# LN_LASER_PS.net
KiCad netlist of a schematic drawn in Altium Designer
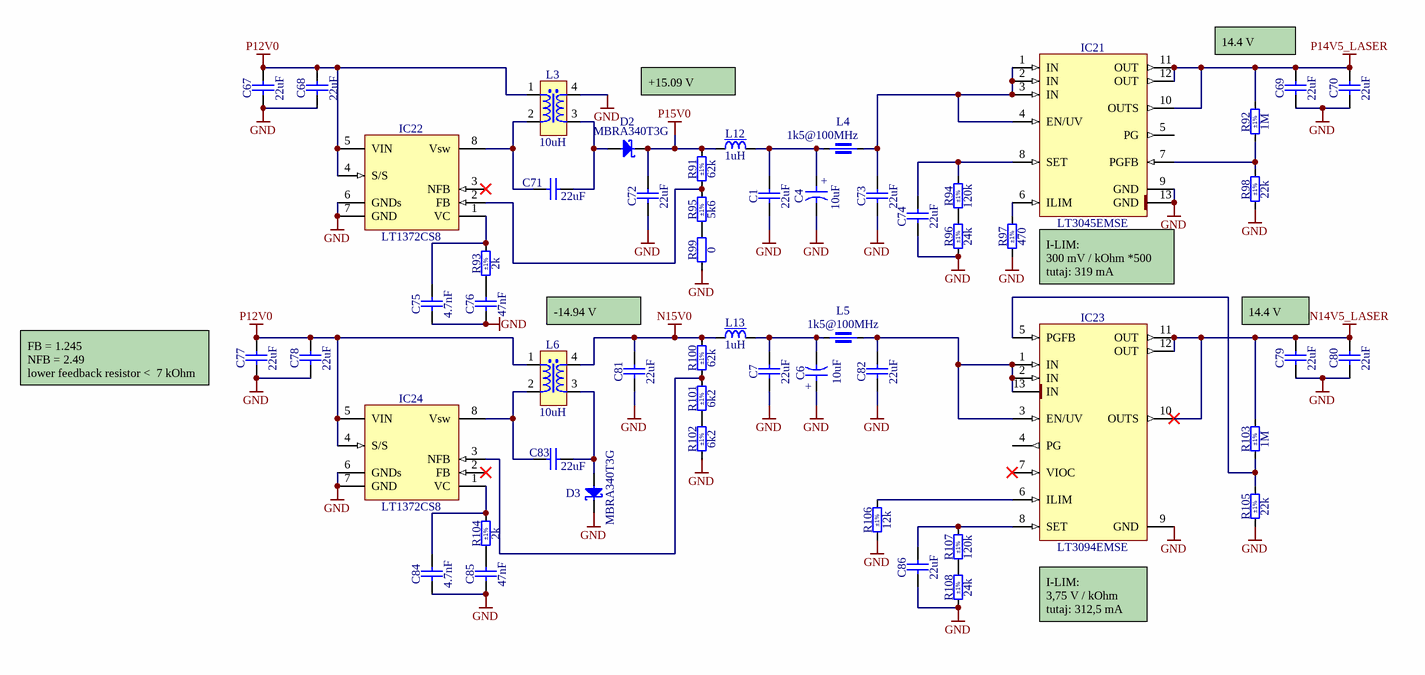
[diagram p0: LN_LASER_PS.SchDoc]

(export (version "E")
  (design (tool "Eeschema 10.0.6"))
  (components
    (comp (ref "C1")
      (value "22uF")
      (footprint "CAPC3216X180N")
      (description "Non-polarised capacitor")
      (fields
        (field (name "PART NUMBER") "CC1206_22UF_35V_20%_JB_TDK_C3216JB1V226M160AC")
        (field (name "VOLTAGE") "35V")
        (field (name "AUTHOR") "CERN DEM JLC")
      )
      (libsource (lib "Capacitors") (part "Capacitor - non polarized"))
    )
    (comp (ref "C4")
      (value "10uF")
      (footprint "CAPMP3528X210N")
      (description "Polarised capacitor")
      (fields
        (field (name "PART NUMBER") "CTE3528-21_10UF_20V_10%_AVX_TPSB106K020T0500")
        (field (name "VOLTAGE") "20V")
        (field (name "AUTHOR") "CERN DEM JLC")
      )
      (libsource (lib "Capacitors") (part "Capacitor - polarized"))
    )
    (comp (ref "C6")
      (value "10uF")
      (footprint "CAPMP3528X210N")
      (description "Polarised capacitor")
      (fields
        (field (name "PART NUMBER") "CTE3528-21_10UF_20V_10%_AVX_TPSB106K020T0500")
        (field (name "VOLTAGE") "20V")
        (field (name "AUTHOR") "CERN DEM JLC")
      )
      (libsource (lib "Capacitors") (part "Capacitor - polarized"))
    )
    (comp (ref "C7")
      (value "22uF")
      (footprint "CAPC3216X180N")
      (description "Non-polarised capacitor")
      (fields
        (field (name "PART NUMBER") "CC1206_22UF_35V_20%_JB_TDK_C3216JB1V226M160AC")
        (field (name "VOLTAGE") "35V")
        (field (name "AUTHOR") "CERN DEM JLC")
      )
      (libsource (lib "Capacitors") (part "Capacitor - non polarized"))
    )
    (comp (ref "C67")
      (value "22uF")
      (footprint "CAPC3216X180N")
      (description "Non-polarised capacitor")
      (fields
        (field (name "PART NUMBER") "CC1206_22UF_35V_20%_JB_TDK_C3216JB1V226M160AC")
        (field (name "VOLTAGE") "35V")
        (field (name "AUTHOR") "CERN DEM JLC")
      )
      (libsource (lib "Capacitors") (part "Capacitor - non polarized"))
    )
    (comp (ref "C68")
      (value "22uF")
      (footprint "CAPC3216X180N")
      (description "Non-polarised capacitor")
      (fields
        (field (name "PART NUMBER") "CC1206_22UF_35V_20%_JB_TDK_C3216JB1V226M160AC")
        (field (name "VOLTAGE") "35V")
        (field (name "AUTHOR") "CERN DEM JLC")
      )
      (libsource (lib "Capacitors") (part "Capacitor - non polarized"))
    )
    (comp (ref "C69")
      (value "22uF")
      (footprint "CAPC3216X180N")
      (description "Non-polarised capacitor")
      (fields
        (field (name "PART NUMBER") "CC1206_22UF_35V_20%_JB_TDK_C3216JB1V226M160AC")
        (field (name "VOLTAGE") "35V")
        (field (name "AUTHOR") "CERN DEM JLC")
      )
      (libsource (lib "Capacitors") (part "Capacitor - non polarized"))
    )
    (comp (ref "C70")
      (value "22uF")
      (footprint "CAPC3216X180N")
      (description "Non-polarised capacitor")
      (fields
        (field (name "PART NUMBER") "CC1206_22UF_35V_20%_JB_TDK_C3216JB1V226M160AC")
        (field (name "VOLTAGE") "35V")
        (field (name "AUTHOR") "CERN DEM JLC")
      )
      (libsource (lib "Capacitors") (part "Capacitor - non polarized"))
    )
    (comp (ref "C71")
      (value "22uF")
      (footprint "CAPC3216X180N")
      (description "Non-polarised capacitor")
      (fields
        (field (name "PART NUMBER") "CC1206_22UF_35V_20%_JB_TDK_C3216JB1V226M160AC")
        (field (name "VOLTAGE") "35V")
        (field (name "AUTHOR") "CERN DEM JLC")
      )
      (libsource (lib "Capacitors") (part "Capacitor - non polarized"))
    )
    (comp (ref "C72")
      (value "22uF")
      (footprint "CAPC3216X180N")
      (description "Non-polarised capacitor")
      (fields
        (field (name "PART NUMBER") "CC1206_22UF_35V_20%_JB_TDK_C3216JB1V226M160AC")
        (field (name "VOLTAGE") "35V")
        (field (name "AUTHOR") "CERN DEM JLC")
      )
      (libsource (lib "Capacitors") (part "Capacitor - non polarized"))
    )
    (comp (ref "C73")
      (value "22uF")
      (footprint "CAPC3216X180N")
      (description "Non-polarised capacitor")
      (fields
        (field (name "PART NUMBER") "CC1206_22UF_35V_20%_JB_TDK_C3216JB1V226M160AC")
        (field (name "VOLTAGE") "35V")
        (field (name "AUTHOR") "CERN DEM JLC")
      )
      (libsource (lib "Capacitors") (part "Capacitor - non polarized"))
    )
    (comp (ref "C74")
      (value "22uF")
      (footprint "CAPC3216X180N")
      (description "Non-polarised capacitor")
      (fields
        (field (name "PART NUMBER") "CC1206_22UF_35V_20%_JB_TDK_C3216JB1V226M160AC")
        (field (name "VOLTAGE") "35V")
        (field (name "AUTHOR") "CERN DEM JLC")
      )
      (libsource (lib "Capacitors") (part "Capacitor - non polarized"))
    )
    (comp (ref "C75")
      (value "4.7nF")
      (footprint "CAPC1005X55N")
      (description "Non-polarised capacitor")
      (fields
        (field (name "PART NUMBER") "CC0402_4.7NF_16V_10%_X7R")
        (field (name "VOLTAGE") "16V")
        (field (name "AUTHOR") "CERN DEM JLC")
      )
      (libsource (lib "Capacitors") (part "Capacitor - non polarized"))
    )
    (comp (ref "C76")
      (value "47nF")
      (footprint "CAPC1005X55N")
      (description "Non-polarised capacitor")
      (fields
        (field (name "PART NUMBER") "CC0402_47NF_25V_10%_X7R")
        (field (name "VOLTAGE") "25V")
        (field (name "AUTHOR") "CERN DEM JLC")
      )
      (libsource (lib "Capacitors") (part "Capacitor - non polarized"))
    )
    (comp (ref "C77")
      (value "22uF")
      (footprint "CAPC3216X180N")
      (description "Non-polarised capacitor")
      (fields
        (field (name "PART NUMBER") "CC1206_22UF_35V_20%_JB_TDK_C3216JB1V226M160AC")
        (field (name "VOLTAGE") "35V")
        (field (name "AUTHOR") "CERN DEM JLC")
      )
      (libsource (lib "Capacitors") (part "Capacitor - non polarized"))
    )
    (comp (ref "C78")
      (value "22uF")
      (footprint "CAPC3216X180N")
      (description "Non-polarised capacitor")
      (fields
        (field (name "PART NUMBER") "CC1206_22UF_35V_20%_JB_TDK_C3216JB1V226M160AC")
        (field (name "VOLTAGE") "35V")
        (field (name "AUTHOR") "CERN DEM JLC")
      )
      (libsource (lib "Capacitors") (part "Capacitor - non polarized"))
    )
    (comp (ref "C79")
      (value "22uF")
      (footprint "CAPC3216X180N")
      (description "Non-polarised capacitor")
      (fields
        (field (name "PART NUMBER") "CC1206_22UF_35V_20%_JB_TDK_C3216JB1V226M160AC")
        (field (name "VOLTAGE") "35V")
        (field (name "AUTHOR") "CERN DEM JLC")
      )
      (libsource (lib "Capacitors") (part "Capacitor - non polarized"))
    )
    (comp (ref "C80")
      (value "22uF")
      (footprint "CAPC3216X180N")
      (description "Non-polarised capacitor")
      (fields
        (field (name "PART NUMBER") "CC1206_22UF_35V_20%_JB_TDK_C3216JB1V226M160AC")
        (field (name "VOLTAGE") "35V")
        (field (name "AUTHOR") "CERN DEM JLC")
      )
      (libsource (lib "Capacitors") (part "Capacitor - non polarized"))
    )
    (comp (ref "C81")
      (value "22uF")
      (footprint "CAPC3216X180N")
      (description "Non-polarised capacitor")
      (fields
        (field (name "PART NUMBER") "CC1206_22UF_35V_20%_JB_TDK_C3216JB1V226M160AC")
        (field (name "VOLTAGE") "35V")
        (field (name "AUTHOR") "CERN DEM JLC")
      )
      (libsource (lib "Capacitors") (part "Capacitor - non polarized"))
    )
    (comp (ref "C82")
      (value "22uF")
      (footprint "CAPC3216X180N")
      (description "Non-polarised capacitor")
      (fields
        (field (name "PART NUMBER") "CC1206_22UF_35V_20%_JB_TDK_C3216JB1V226M160AC")
        (field (name "VOLTAGE") "35V")
        (field (name "AUTHOR") "CERN DEM JLC")
      )
      (libsource (lib "Capacitors") (part "Capacitor - non polarized"))
    )
    (comp (ref "C83")
      (value "22uF")
      (footprint "CAPC3216X180N")
      (description "Non-polarised capacitor")
      (fields
        (field (name "PART NUMBER") "CC1206_22UF_35V_20%_JB_TDK_C3216JB1V226M160AC")
        (field (name "VOLTAGE") "35V")
        (field (name "AUTHOR") "CERN DEM JLC")
      )
      (libsource (lib "Capacitors") (part "Capacitor - non polarized"))
    )
    (comp (ref "C84")
      (value "4.7nF")
      (footprint "CAPC1005X55N")
      (description "Non-polarised capacitor")
      (fields
        (field (name "PART NUMBER") "CC0402_4.7NF_16V_10%_X7R")
        (field (name "VOLTAGE") "16V")
        (field (name "AUTHOR") "CERN DEM JLC")
      )
      (libsource (lib "Capacitors") (part "Capacitor - non polarized"))
    )
    (comp (ref "C85")
      (value "47nF")
      (footprint "CAPC1005X55N")
      (description "Non-polarised capacitor")
      (fields
        (field (name "PART NUMBER") "CC0402_47NF_25V_10%_X7R")
        (field (name "VOLTAGE") "25V")
        (field (name "AUTHOR") "CERN DEM JLC")
      )
      (libsource (lib "Capacitors") (part "Capacitor - non polarized"))
    )
    (comp (ref "C86")
      (value "22uF")
      (footprint "CAPC3216X180N")
      (description "Non-polarised capacitor")
      (fields
        (field (name "PART NUMBER") "CC1206_22UF_35V_20%_JB_TDK_C3216JB1V226M160AC")
        (field (name "VOLTAGE") "35V")
        (field (name "AUTHOR") "CERN DEM JLC")
      )
      (libsource (lib "Capacitors") (part "Capacitor - non polarized"))
    )
    (comp (ref "D2")
      (value "MBRA340T3G")
      (footprint "DIOM5226X220N")
      (description "Schottky Diode")
      (fields
        (field (name "VOLTAGE") "40V")
        (field (name "POWER") "3A")
        (field (name "AUTHOR") "CERN DEM JLC")
      )
      (libsource (lib "ICs And Semiconductors") (part "Diode Schottky"))
    )
    (comp (ref "D3")
      (value "MBRA340T3G")
      (footprint "DIOM5226X220N")
      (description "Schottky Diode")
      (fields
        (field (name "VOLTAGE") "40V")
        (field (name "POWER") "3A")
        (field (name "AUTHOR") "CERN DEM JLC")
      )
      (libsource (lib "ICs And Semiconductors") (part "Diode Schottky"))
    )
    (comp (ref "IC21")
      (value "LT3045EMSE")
      (footprint "SOP65P490X110-13N-R175X294")
      (description "20V, 500mA, Ultralow Noise, Ultrahigh PSRR Linear Regulator")
      (fields (field (name "MANUFACTURER") "LINEAR TECHNOLOGY") (field (name "AUTHOR") "CERN DEM HF"))
      (libsource (lib "ICs And Semiconductors") (part "LT3045"))
    )
    (comp (ref "IC22")
      (value "LT1372CS8")
      (footprint "SOIC127P600X175-8N")
      (description "500kHz, 1.5A, High Efficiency, 1.5A Switching Regulators")
      (fields (field (name "MANUFACTURER") "LINEAR TECHNOLOGY") (field (name "AUTHOR") "CERN DEM HF"))
      (libsource (lib "ICs And Semiconductors") (part "LT137x"))
    )
    (comp (ref "IC23")
      (value "LT3094EMSE")
      (footprint "SOP65P490X110-13N-R175X294")
      (description "-20V, 500mA, Ultralow Noise, Ultrahigh PSRR Negative Linear Regulator")
      (fields
        (field (name "PART NUMBER") "LT3094EMSE#PBF")
        (field (name "MANUFACTURER") "LINEAR TECHNOLOGY")
        (field (name "AUTHOR") "CERN DEM JLC")
      )
      (libsource (lib "ICs And Semiconductors") (part "LT3094"))
    )
    (comp (ref "IC24")
      (value "LT1372CS8")
      (footprint "SOIC127P600X175-8N")
      (description "500kHz, 1.5A, High Efficiency, 1.5A Switching Regulators")
      (fields (field (name "MANUFACTURER") "LINEAR TECHNOLOGY") (field (name "AUTHOR") "CERN DEM HF"))
      (libsource (lib "ICs And Semiconductors") (part "LT137x"))
    )
    (comp (ref "L3")
      (value "10uH")
      (footprint "IND_COOPER_CTX-1A")
      (description "Dual Winding Shielded Power Inductor/Transformer CTX OCTA-PAC® PLUS Serie")
      (fields
        (field (name "PART NUMBER") "IND_COOPER_CTX10-1A-R")
        (field (name "TOLERANCE") "±25%")
        (field (name "AUTHOR") "CERN DEM JLC")
      )
      (libsource (lib "Inductors & Transformers") (part "IND_COOPER_CTX"))
    )
    (comp (ref "L4")
      (value "1k5@100MHz")
      (footprint "INDC2012X110N")
      (fields
        (field (name "PART NUMBER") "IND0805_WURTH_742792097")
        (field (name "POWER") "1A")
        (field (name "TOLERANCE") "±25%")
        (field (name "AUTHOR") "CERN DEM MR")
      )
      (libsource (lib "Inductors & Transformers") (part "Ferrite Bead"))
    )
    (comp (ref "L5")
      (value "1k5@100MHz")
      (footprint "INDC2012X110N")
      (fields
        (field (name "PART NUMBER") "IND0805_WURTH_742792097")
        (field (name "POWER") "1A")
        (field (name "TOLERANCE") "±25%")
        (field (name "AUTHOR") "CERN DEM MR")
      )
      (libsource (lib "Inductors & Transformers") (part "Ferrite Bead"))
    )
    (comp (ref "L6")
      (value "10uH")
      (footprint "IND_COOPER_CTX-1A")
      (description "Dual Winding Shielded Power Inductor/Transformer CTX OCTA-PAC® PLUS Serie")
      (fields
        (field (name "PART NUMBER") "IND_COOPER_CTX10-1A-R")
        (field (name "TOLERANCE") "±25%")
        (field (name "AUTHOR") "CERN DEM JLC")
      )
      (libsource (lib "Inductors & Transformers") (part "IND_COOPER_CTX"))
    )
    (comp (ref "L12")
      (value "1uH")
      (footprint "INDM3225X210N")
      (description "Inductor With Core")
      (fields
        (field (name "PART NUMBER") "IND1210_1UH_10%_EPCOS_B82422A")
        (field (name "POWER") "380mA")
        (field (name "AUTHOR") "CERN DEM JLC")
      )
      (libsource (lib "Inductors & Transformers") (part "Inductor With Magnetic core"))
    )
    (comp (ref "L13")
      (value "1uH")
      (footprint "INDM3225X210N")
      (description "Inductor With Core")
      (fields
        (field (name "PART NUMBER") "IND1210_1UH_10%_EPCOS_B82422A")
        (field (name "POWER") "380mA")
        (field (name "AUTHOR") "CERN DEM JLC")
      )
      (libsource (lib "Inductors & Transformers") (part "Inductor With Magnetic core"))
    )
    (comp (ref "R91")
      (value "62k")
      (footprint "RESC1005X40N")
      (description "Resistor - 1%")
      (fields
        (field (name "TOLERANCE") "±1%")
        (field (name "PART NUMBER") "R0402_62K_1%_0.0625W_100PPM")
        (field (name "POWER") "0.0625W")
        (field (name "AUTHOR") "CERN DEM JLC")
      )
      (libsource (lib "Resistors") (part "Resistor - 1%"))
    )
    (comp (ref "R92")
      (value "1M")
      (footprint "RESC1005X40N")
      (description "Resistor - 1%")
      (fields
        (field (name "TOLERANCE") "±1%")
        (field (name "PART NUMBER") "R0402_1M_1%_0.0625W_100PPM")
        (field (name "POWER") "0.0625W")
        (field (name "AUTHOR") "CERN DEM JLC")
      )
      (libsource (lib "Resistors") (part "Resistor - 1%"))
    )
    (comp (ref "R93")
      (value "2k")
      (footprint "RESC1005X40N")
      (description "Resistor - 1%")
      (fields
        (field (name "TOLERANCE") "±1%")
        (field (name "PART NUMBER") "R0402_2K_1%_0.0625W_100PPM")
        (field (name "POWER") "0.0625W")
        (field (name "AUTHOR") "CERN DEM JLC")
      )
      (libsource (lib "Resistors") (part "Resistor - 1%"))
    )
    (comp (ref "R94")
      (value "120k")
      (footprint "RESC1608X55N")
      (description "Resistor - 1%")
      (fields
        (field (name "TOLERANCE") "±1%")
        (field (name "PART NUMBER") "R0603_120K_1%_0.1W_100PPM")
        (field (name "POWER") "0.1W")
        (field (name "AUTHOR") "CERN DEM JLC")
      )
      (libsource (lib "Resistors") (part "Resistor - 1%"))
    )
    (comp (ref "R95")
      (value "5k6")
      (footprint "RESC1005X40N")
      (description "Resistor - 1%")
      (fields
        (field (name "TOLERANCE") "±1%")
        (field (name "PART NUMBER") "R0402_5K6_1%_0.0625W_100PPM")
        (field (name "POWER") "0.0625W")
        (field (name "AUTHOR") "CERN DEM JLC")
      )
      (libsource (lib "Resistors") (part "Resistor - 1%"))
    )
    (comp (ref "R96")
      (value "24k")
      (footprint "RESC1608X55N")
      (description "Resistor - 1%")
      (fields
        (field (name "TOLERANCE") "±1%")
        (field (name "PART NUMBER") "R0603_24K_1%_0.1W_100PPM")
        (field (name "POWER") "0.1W")
        (field (name "AUTHOR") "CERN DEM JLC")
      )
      (libsource (lib "Resistors") (part "Resistor - 1%"))
    )
    (comp (ref "R97")
      (value "470")
      (footprint "RESC1005X40N")
      (description "Resistor - 1%")
      (fields
        (field (name "TOLERANCE") "±1%")
        (field (name "PART NUMBER") "R0402_470R_1%_0.0625W_100PPM")
        (field (name "POWER") "0.0625W")
        (field (name "AUTHOR") "CERN DEM JLC")
      )
      (libsource (lib "Resistors") (part "Resistor - 1%"))
    )
    (comp (ref "R98")
      (value "22k")
      (footprint "RESC1005X40N")
      (description "Resistor - 1%")
      (fields
        (field (name "TOLERANCE") "±1%")
        (field (name "PART NUMBER") "R0402_22K_1%_0.0625W_100PPM")
        (field (name "POWER") "0.0625W")
        (field (name "AUTHOR") "CERN DEM JLC")
      )
      (libsource (lib "Resistors") (part "Resistor - 1%"))
    )
    (comp (ref "R99")
      (value "0")
      (footprint "RESC1005X40N")
      (description "Resistor")
      (fields
        (field (name "PART NUMBER") "R0402_0R_JUMPER")
        (field (name "MANUFACTURER") "GENERIC")
        (field (name "AUTHOR") "CERN DEM JLC")
      )
      (libsource (lib "Resistors") (part "Resistor"))
    )
    (comp (ref "R100")
      (value "62k")
      (footprint "RESC1005X40N")
      (description "Resistor - 1%")
      (fields
        (field (name "TOLERANCE") "±1%")
        (field (name "PART NUMBER") "R0402_62K_1%_0.0625W_100PPM")
        (field (name "POWER") "0.0625W")
        (field (name "AUTHOR") "CERN DEM JLC")
      )
      (libsource (lib "Resistors") (part "Resistor - 1%"))
    )
    (comp (ref "R101")
      (value "6k2")
      (footprint "RESC1005X40N")
      (description "Resistor - 1%")
      (fields
        (field (name "TOLERANCE") "±1%")
        (field (name "PART NUMBER") "R0402_6K2_1%_0.0625W_100PPM")
        (field (name "POWER") "0.0625W")
        (field (name "AUTHOR") "CERN DEM JLC")
      )
      (libsource (lib "Resistors") (part "Resistor - 1%"))
    )
    (comp (ref "R102")
      (value "6k2")
      (footprint "RESC1005X40N")
      (description "Resistor - 1%")
      (fields
        (field (name "TOLERANCE") "±1%")
        (field (name "PART NUMBER") "R0402_6K2_1%_0.0625W_100PPM")
        (field (name "POWER") "0.0625W")
        (field (name "AUTHOR") "CERN DEM JLC")
      )
      (libsource (lib "Resistors") (part "Resistor - 1%"))
    )
    (comp (ref "R103")
      (value "1M")
      (footprint "RESC1005X40N")
      (description "Resistor - 1%")
      (fields
        (field (name "TOLERANCE") "±1%")
        (field (name "PART NUMBER") "R0402_1M_1%_0.0625W_100PPM")
        (field (name "POWER") "0.0625W")
        (field (name "AUTHOR") "CERN DEM JLC")
      )
      (libsource (lib "Resistors") (part "Resistor - 1%"))
    )
    (comp (ref "R104")
      (value "2k")
      (footprint "RESC1005X40N")
      (description "Resistor - 1%")
      (fields
        (field (name "TOLERANCE") "±1%")
        (field (name "PART NUMBER") "R0402_2K_1%_0.0625W_100PPM")
        (field (name "POWER") "0.0625W")
        (field (name "AUTHOR") "CERN DEM JLC")
      )
      (libsource (lib "Resistors") (part "Resistor - 1%"))
    )
    (comp (ref "R105")
      (value "22k")
      (footprint "RESC1005X40N")
      (description "Resistor - 1%")
      (fields
        (field (name "TOLERANCE") "±1%")
        (field (name "PART NUMBER") "R0402_22K_1%_0.0625W_100PPM")
        (field (name "POWER") "0.0625W")
        (field (name "AUTHOR") "CERN DEM JLC")
      )
      (libsource (lib "Resistors") (part "Resistor - 1%"))
    )
    (comp (ref "R106")
      (value "12k")
      (footprint "RESC1005X40N")
      (description "Resistor - 1%")
      (fields
        (field (name "TOLERANCE") "±1%")
        (field (name "PART NUMBER") "R0402_12K_1%_0.0625W_100PPM")
        (field (name "POWER") "0.0625W")
        (field (name "AUTHOR") "CERN DEM JLC")
      )
      (libsource (lib "Resistors") (part "Resistor - 1%"))
    )
    (comp (ref "R107")
      (value "120k")
      (footprint "RESC1608X55N")
      (description "Resistor - 1%")
      (fields
        (field (name "TOLERANCE") "±1%")
        (field (name "PART NUMBER") "R0603_120K_1%_0.1W_100PPM")
        (field (name "POWER") "0.1W")
        (field (name "AUTHOR") "CERN DEM JLC")
      )
      (libsource (lib "Resistors") (part "Resistor - 1%"))
    )
    (comp (ref "R108")
      (value "24k")
      (footprint "RESC1608X55N")
      (description "Resistor - 1%")
      (fields
        (field (name "TOLERANCE") "±1%")
        (field (name "PART NUMBER") "R0603_24K_1%_0.1W_100PPM")
        (field (name "POWER") "0.1W")
        (field (name "AUTHOR") "CERN DEM JLC")
      )
      (libsource (lib "Resistors") (part "Resistor - 1%"))
    )
  )
  (nets
    (net (code "1") (name "GND") (class "Default")
      (node (ref "C1") (pin "1") (pinfunction "1_1") (pintype "passive"))
      (node (ref "C4") (pin "2") (pinfunction "2_2") (pintype "passive"))
      (node (ref "C6") (pin "1") (pinfunction "1_1") (pintype "passive"))
      (node (ref "C67") (pin "1") (pinfunction "1_1") (pintype "passive"))
      (node (ref "C68") (pin "1") (pinfunction "1_1") (pintype "passive"))
      (node (ref "C69") (pin "1") (pinfunction "1_1") (pintype "passive"))
      (node (ref "C7") (pin "1") (pinfunction "1_1") (pintype "passive"))
      (node (ref "C70") (pin "1") (pinfunction "1_1") (pintype "passive"))
      (node (ref "C72") (pin "1") (pinfunction "1_1") (pintype "passive"))
      (node (ref "C73") (pin "1") (pinfunction "1_1") (pintype "passive"))
      (node (ref "C74") (pin "1") (pinfunction "1_1") (pintype "passive"))
      (node (ref "C75") (pin "1") (pinfunction "1_1") (pintype "passive"))
      (node (ref "C76") (pin "1") (pinfunction "1_1") (pintype "passive"))
      (node (ref "C77") (pin "1") (pinfunction "1_1") (pintype "passive"))
      (node (ref "C78") (pin "1") (pinfunction "1_1") (pintype "passive"))
      (node (ref "C79") (pin "1") (pinfunction "1_1") (pintype "passive"))
      (node (ref "C80") (pin "1") (pinfunction "1_1") (pintype "passive"))
      (node (ref "C81") (pin "1") (pinfunction "1_1") (pintype "passive"))
      (node (ref "C82") (pin "1") (pinfunction "1_1") (pintype "passive"))
      (node (ref "C84") (pin "1") (pinfunction "1_1") (pintype "passive"))
      (node (ref "C85") (pin "1") (pinfunction "1_1") (pintype "passive"))
      (node (ref "C86") (pin "1") (pinfunction "1_1") (pintype "passive"))
      (node (ref "D3") (pin "1") (pinfunction "C_1") (pintype "passive"))
      (node (ref "IC21") (pin "13") (pinfunction "GND_13") (pintype "power_in"))
      (node (ref "IC21") (pin "9") (pinfunction "GND_9") (pintype "power_in"))
      (node (ref "IC22") (pin "6") (pinfunction "GNDs_6") (pintype "power_in"))
      (node (ref "IC22") (pin "7") (pinfunction "GND_7") (pintype "power_in"))
      (node (ref "IC23") (pin "9") (pinfunction "GND_9") (pintype "power_in"))
      (node (ref "IC24") (pin "6") (pinfunction "GNDs_6") (pintype "power_in"))
      (node (ref "IC24") (pin "7") (pinfunction "GND_7") (pintype "power_in"))
      (node (ref "L3") (pin "4") (pinfunction "4_4") (pintype "passive"))
      (node (ref "R102") (pin "1") (pinfunction "1_1") (pintype "passive"))
      (node (ref "R105") (pin "1") (pinfunction "1_1") (pintype "passive"))
      (node (ref "R106") (pin "1") (pinfunction "1_1") (pintype "passive"))
      (node (ref "R108") (pin "1") (pinfunction "1_1") (pintype "passive"))
      (node (ref "R96") (pin "1") (pinfunction "1_1") (pintype "passive"))
      (node (ref "R97") (pin "1") (pinfunction "1_1") (pintype "passive"))
      (node (ref "R98") (pin "1") (pinfunction "1_1") (pintype "passive"))
      (node (ref "R99") (pin "1") (pinfunction "1_1") (pintype "passive"))
    )
    (net (code "2") (name "N14V5_LASER") (class "Default")
      (node (ref "C79") (pin "2") (pinfunction "2_2") (pintype "passive"))
      (node (ref "C80") (pin "2") (pinfunction "2_2") (pintype "passive"))
      (node (ref "IC23") (pin "10") (pinfunction "OUTS_10") (pintype "output"))
      (node (ref "IC23") (pin "11") (pinfunction "OUT_11") (pintype "output"))
      (node (ref "IC23") (pin "12") (pinfunction "OUT_12") (pintype "output"))
      (node (ref "R103") (pin "2") (pinfunction "2_2") (pintype "passive"))
    )
    (net (code "3") (name "N15V0") (class "Default")
      (node (ref "C81") (pin "2") (pinfunction "2_2") (pintype "passive"))
      (node (ref "L13") (pin "1") (pinfunction "1_1") (pintype "passive"))
      (node (ref "L6") (pin "4") (pinfunction "4_4") (pintype "passive"))
      (node (ref "R100") (pin "2") (pinfunction "2_2") (pintype "passive"))
    )
    (net (code "4") (name "Net-(C1-Pad2)") (class "Default")
      (node (ref "C1") (pin "2") (pinfunction "2_2") (pintype "passive"))
      (node (ref "C4") (pin "1") (pinfunction "1_1") (pintype "passive"))
      (node (ref "L12") (pin "2") (pinfunction "2_2") (pintype "passive"))
      (node (ref "L4") (pin "1") (pinfunction "1_1") (pintype "passive"))
    )
    (net (code "5") (name "Net-(C6-Pad2)") (class "Default")
      (node (ref "C6") (pin "2") (pinfunction "2_2") (pintype "passive"))
      (node (ref "C7") (pin "2") (pinfunction "2_2") (pintype "passive"))
      (node (ref "L13") (pin "2") (pinfunction "2_2") (pintype "passive"))
      (node (ref "L5") (pin "1") (pinfunction "1_1") (pintype "passive"))
    )
    (net (code "6") (name "Net-(C76-Pad2)") (class "Default")
      (node (ref "C76") (pin "2") (pinfunction "2_2") (pintype "passive"))
      (node (ref "R93") (pin "1") (pinfunction "1_1") (pintype "passive"))
    )
    (net (code "7") (name "Net-(C85-Pad2)") (class "Default")
      (node (ref "C85") (pin "2") (pinfunction "2_2") (pintype "passive"))
      (node (ref "R104") (pin "1") (pinfunction "1_1") (pintype "passive"))
    )
    (net (code "8") (name "Net-(D2-A)") (class "Default")
      (node (ref "C71") (pin "1") (pinfunction "1_1") (pintype "passive"))
      (node (ref "D2") (pin "2") (pinfunction "A_2") (pintype "passive"))
      (node (ref "L3") (pin "3") (pinfunction "3_3") (pintype "passive"))
    )
    (net (code "9") (name "Net-(D3-A)") (class "Default")
      (node (ref "C83") (pin "1") (pinfunction "1_1") (pintype "passive"))
      (node (ref "D3") (pin "2") (pinfunction "A_2") (pintype "passive"))
      (node (ref "L6") (pin "3") (pinfunction "3_3") (pintype "passive"))
    )
    (net (code "10") (name "Net-(IC21-EN{slash}UV)") (class "Default")
      (node (ref "C73") (pin "2") (pinfunction "2_2") (pintype "passive"))
      (node (ref "IC21") (pin "1") (pinfunction "IN_1") (pintype "input"))
      (node (ref "IC21") (pin "2") (pinfunction "IN_2") (pintype "input"))
      (node (ref "IC21") (pin "3") (pinfunction "IN_3") (pintype "input"))
      (node (ref "IC21") (pin "4") (pinfunction "EN/UV_4") (pintype "input"))
      (node (ref "L4") (pin "2") (pinfunction "2_2") (pintype "passive"))
    )
    (net (code "11") (name "Net-(IC21-ILIM)") (class "Default")
      (node (ref "IC21") (pin "6") (pinfunction "ILIM_6") (pintype "input"))
      (node (ref "R97") (pin "2") (pinfunction "2_2") (pintype "passive"))
    )
    (net (code "12") (name "Net-(IC21-PGFB)") (class "Default")
      (node (ref "IC21") (pin "7") (pinfunction "PGFB_7") (pintype "input"))
      (node (ref "R92") (pin "1") (pinfunction "1_1") (pintype "passive"))
      (node (ref "R98") (pin "2") (pinfunction "2_2") (pintype "passive"))
    )
    (net (code "13") (name "Net-(IC21-SET)") (class "Default")
      (node (ref "C74") (pin "2") (pinfunction "2_2") (pintype "passive"))
      (node (ref "IC21") (pin "8") (pinfunction "SET_8") (pintype "input"))
      (node (ref "R94") (pin "2") (pinfunction "2_2") (pintype "passive"))
    )
    (net (code "14") (name "Net-(IC22-FB)") (class "Default")
      (node (ref "IC22") (pin "2") (pinfunction "FB_2") (pintype "input"))
      (node (ref "R91") (pin "1") (pinfunction "1_1") (pintype "passive"))
      (node (ref "R95") (pin "2") (pinfunction "2_2") (pintype "passive"))
    )
    (net (code "15") (name "Net-(IC22-VC)") (class "Default")
      (node (ref "C75") (pin "2") (pinfunction "2_2") (pintype "passive"))
      (node (ref "IC22") (pin "1") (pinfunction "VC_1") (pintype "passive"))
      (node (ref "R93") (pin "2") (pinfunction "2_2") (pintype "passive"))
    )
    (net (code "16") (name "Net-(IC22-Vsw)") (class "Default")
      (node (ref "C71") (pin "2") (pinfunction "2_2") (pintype "passive"))
      (node (ref "IC22") (pin "8") (pinfunction "Vsw_8") (pintype "power_in"))
      (node (ref "L3") (pin "2") (pinfunction "2_2") (pintype "passive"))
    )
    (net (code "17") (name "Net-(IC23-EN{slash}UV)") (class "Default")
      (node (ref "C82") (pin "2") (pinfunction "2_2") (pintype "passive"))
      (node (ref "IC23") (pin "1") (pinfunction "IN_1") (pintype "input"))
      (node (ref "IC23") (pin "13") (pinfunction "IN_13") (pintype "power_in"))
      (node (ref "IC23") (pin "2") (pinfunction "IN_2") (pintype "input"))
      (node (ref "IC23") (pin "3") (pinfunction "EN/UV_3") (pintype "input"))
      (node (ref "L5") (pin "2") (pinfunction "2_2") (pintype "passive"))
    )
    (net (code "18") (name "Net-(IC23-ILIM)") (class "Default")
      (node (ref "IC23") (pin "6") (pinfunction "ILIM_6") (pintype "input"))
      (node (ref "R106") (pin "2") (pinfunction "2_2") (pintype "passive"))
    )
    (net (code "19") (name "Net-(IC23-PGFB)") (class "Default")
      (node (ref "IC23") (pin "5") (pinfunction "PGFB_5") (pintype "input"))
      (node (ref "R103") (pin "1") (pinfunction "1_1") (pintype "passive"))
      (node (ref "R105") (pin "2") (pinfunction "2_2") (pintype "passive"))
    )
    (net (code "20") (name "Net-(IC23-SET)") (class "Default")
      (node (ref "C86") (pin "2") (pinfunction "2_2") (pintype "passive"))
      (node (ref "IC23") (pin "8") (pinfunction "SET_8") (pintype "input"))
      (node (ref "R107") (pin "2") (pinfunction "2_2") (pintype "passive"))
    )
    (net (code "21") (name "Net-(IC24-NFB)") (class "Default")
      (node (ref "IC24") (pin "3") (pinfunction "NFB_3") (pintype "input"))
      (node (ref "R100") (pin "1") (pinfunction "1_1") (pintype "passive"))
      (node (ref "R101") (pin "2") (pinfunction "2_2") (pintype "passive"))
    )
    (net (code "22") (name "Net-(IC24-VC)") (class "Default")
      (node (ref "C84") (pin "2") (pinfunction "2_2") (pintype "passive"))
      (node (ref "IC24") (pin "1") (pinfunction "VC_1") (pintype "passive"))
      (node (ref "R104") (pin "2") (pinfunction "2_2") (pintype "passive"))
    )
    (net (code "23") (name "Net-(IC24-Vsw)") (class "Default")
      (node (ref "C83") (pin "2") (pinfunction "2_2") (pintype "passive"))
      (node (ref "IC24") (pin "8") (pinfunction "Vsw_8") (pintype "power_in"))
      (node (ref "L6") (pin "2") (pinfunction "2_2") (pintype "passive"))
    )
    (net (code "24") (name "Net-(R94-Pad1)") (class "Default")
      (node (ref "R94") (pin "1") (pinfunction "1_1") (pintype "passive"))
      (node (ref "R96") (pin "2") (pinfunction "2_2") (pintype "passive"))
    )
    (net (code "25") (name "Net-(R95-Pad1)") (class "Default")
      (node (ref "R95") (pin "1") (pinfunction "1_1") (pintype "passive"))
      (node (ref "R99") (pin "2") (pinfunction "2_2") (pintype "passive"))
    )
    (net (code "26") (name "Net-(R101-Pad1)") (class "Default")
      (node (ref "R101") (pin "1") (pinfunction "1_1") (pintype "passive"))
      (node (ref "R102") (pin "2") (pinfunction "2_2") (pintype "passive"))
    )
    (net (code "27") (name "Net-(R107-Pad1)") (class "Default")
      (node (ref "R107") (pin "1") (pinfunction "1_1") (pintype "passive"))
      (node (ref "R108") (pin "2") (pinfunction "2_2") (pintype "passive"))
    )
    (net (code "28") (name "P12V0") (class "Default")
      (node (ref "C67") (pin "2") (pinfunction "2_2") (pintype "passive"))
      (node (ref "C68") (pin "2") (pinfunction "2_2") (pintype "passive"))
      (node (ref "C77") (pin "2") (pinfunction "2_2") (pintype "passive"))
      (node (ref "C78") (pin "2") (pinfunction "2_2") (pintype "passive"))
      (node (ref "IC22") (pin "4") (pinfunction "S/S_4") (pintype "input"))
      (node (ref "IC22") (pin "5") (pinfunction "VIN_5") (pintype "power_in"))
      (node (ref "IC24") (pin "4") (pinfunction "S/S_4") (pintype "input"))
      (node (ref "IC24") (pin "5") (pinfunction "VIN_5") (pintype "power_in"))
      (node (ref "L3") (pin "1") (pinfunction "1_1") (pintype "passive"))
      (node (ref "L6") (pin "1") (pinfunction "1_1") (pintype "passive"))
    )
    (net (code "29") (name "P14V5_LASER") (class "Default")
      (node (ref "C69") (pin "2") (pinfunction "2_2") (pintype "passive"))
      (node (ref "C70") (pin "2") (pinfunction "2_2") (pintype "passive"))
      (node (ref "IC21") (pin "10") (pinfunction "OUTS_10") (pintype "output"))
      (node (ref "IC21") (pin "11") (pinfunction "OUT_11") (pintype "output"))
      (node (ref "IC21") (pin "12") (pinfunction "OUT_12") (pintype "output"))
      (node (ref "R92") (pin "2") (pinfunction "2_2") (pintype "passive"))
    )
    (net (code "30") (name "P15V0") (class "Default")
      (node (ref "C72") (pin "2") (pinfunction "2_2") (pintype "passive"))
      (node (ref "D2") (pin "1") (pinfunction "C_1") (pintype "passive"))
      (node (ref "L12") (pin "1") (pinfunction "1_1") (pintype "passive"))
      (node (ref "R91") (pin "2") (pinfunction "2_2") (pintype "passive"))
    )
    (net (code "31") (name "unconnected-(IC21-PG-Pad5)") (class "Default")
      (node (ref "IC21") (pin "5") (pinfunction "PG_5") (pintype "output"))
    )
    (net (code "32") (name "unconnected-(IC22-NFB-Pad3)") (class "Default")
      (node (ref "IC22") (pin "3") (pinfunction "NFB_3") (pintype "input+no_connect"))
    )
    (net (code "33") (name "unconnected-(IC23-PG-Pad4)") (class "Default")
      (node (ref "IC23") (pin "4") (pinfunction "PG_4") (pintype "output"))
    )
    (net (code "34") (name "unconnected-(IC23-VIOC-Pad7)") (class "Default")
      (node (ref "IC23") (pin "7") (pinfunction "VIOC_7") (pintype "input+no_connect"))
    )
    (net (code "35") (name "unconnected-(IC24-FB-Pad2)") (class "Default")
      (node (ref "IC24") (pin "2") (pinfunction "FB_2") (pintype "input+no_connect"))
    )
  )
)
